# Display_Buttons.net
KiCad netlist of a schematic drawn in Altium Designer
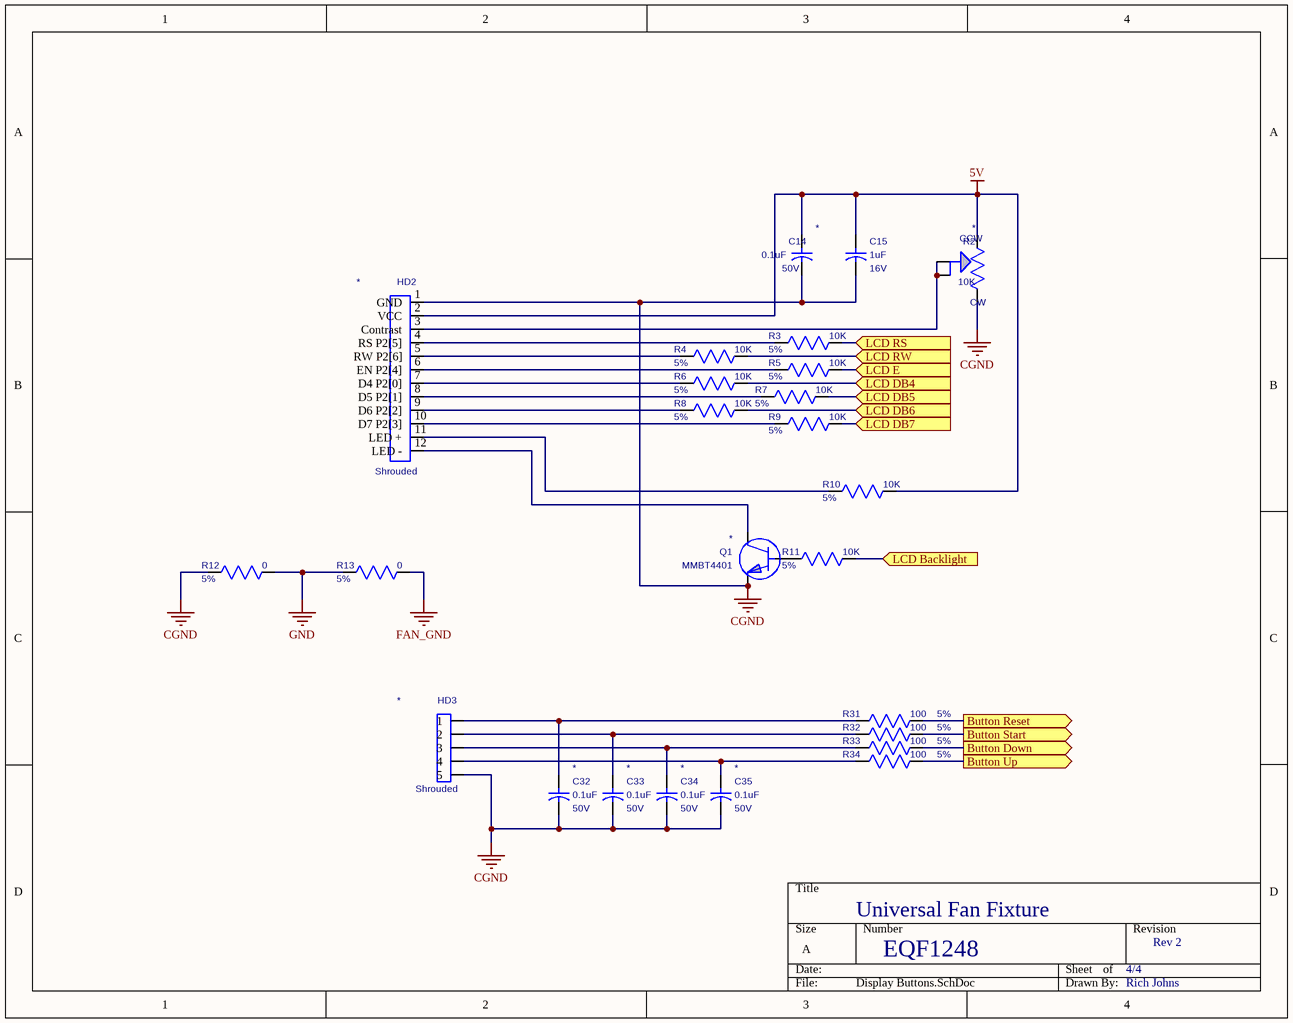
[diagram p0: Display Buttons.SchDoc]

(export (version "E")
  (design (tool "Eeschema 10.0.6"))
  (components
    (comp (ref "C14")
      (value "0.1uF")
      (footprint "0603")
      (fields
        (field (name "DNS") "*")
        (field (name "VOLTAGE") "50V")
        (field (name "TOLERANCE") "+/- 20%")
        (field (name "Comment") "CAP_NON_POLAR_SMT")
        (field (name "CHECKEDBY") "Sam Rhoufiry")
        (field (name "CREATEDBY") "Mike Tyger")
        (field (name "LASTUPDATEDBY") "Mike Tyger")
      )
      (libsource (lib "bome") (part "CAP_NON_POLAR_SMT"))
    )
    (comp (ref "C15")
      (value "1uF")
      (footprint "0603")
      (fields
        (field (name "TOLERANCE") "+/- 10%")
        (field (name "VOLTAGE") "16V")
        (field (name "Comment") "1.0uF_0603_16V")
        (field (name "CHECKEDBY") "gdeguzman")
        (field (name "LASTUPDATEDBY") "Rui Zhang")
      )
      (libsource (lib "bome") (part "1.0uF_0603_16V"))
    )
    (comp (ref "C32")
      (value "0.1uF")
      (footprint "0603")
      (fields
        (field (name "DNS") "*")
        (field (name "VOLTAGE") "50V")
        (field (name "TOLERANCE") "+/- 20%")
        (field (name "Comment") "CAP_NON_POLAR_SMT")
        (field (name "CHECKEDBY") "Sam Rhoufiry")
        (field (name "CREATEDBY") "Mike Tyger")
        (field (name "LASTUPDATEDBY") "Mike Tyger")
      )
      (libsource (lib "bome") (part "CAP_NON_POLAR_SMT"))
    )
    (comp (ref "C33")
      (value "0.1uF")
      (footprint "0603")
      (fields
        (field (name "DNS") "*")
        (field (name "VOLTAGE") "50V")
        (field (name "TOLERANCE") "+/- 20%")
        (field (name "Comment") "CAP_NON_POLAR_SMT")
        (field (name "CHECKEDBY") "Sam Rhoufiry")
        (field (name "CREATEDBY") "Mike Tyger")
        (field (name "LASTUPDATEDBY") "Mike Tyger")
      )
      (libsource (lib "bome") (part "CAP_NON_POLAR_SMT"))
    )
    (comp (ref "C34")
      (value "0.1uF")
      (footprint "0603")
      (fields
        (field (name "DNS") "*")
        (field (name "VOLTAGE") "50V")
        (field (name "TOLERANCE") "+/- 20%")
        (field (name "Comment") "CAP_NON_POLAR_SMT")
        (field (name "CHECKEDBY") "Sam Rhoufiry")
        (field (name "CREATEDBY") "Mike Tyger")
        (field (name "LASTUPDATEDBY") "Mike Tyger")
      )
      (libsource (lib "bome") (part "CAP_NON_POLAR_SMT"))
    )
    (comp (ref "C35")
      (value "0.1uF")
      (footprint "0603")
      (fields
        (field (name "DNS") "*")
        (field (name "VOLTAGE") "50V")
        (field (name "TOLERANCE") "+/- 20%")
        (field (name "Comment") "CAP_NON_POLAR_SMT")
        (field (name "CHECKEDBY") "Sam Rhoufiry")
        (field (name "CREATEDBY") "Mike Tyger")
        (field (name "LASTUPDATEDBY") "Mike Tyger")
      )
      (libsource (lib "bome") (part "CAP_NON_POLAR_SMT"))
    )
    (comp (ref "HD2")
      (value "HDR12PIN100SHRD")
      (footprint "HDR12PIN100SHRD")
      (description "Header, 0.1 in., 12 pins Pins, Shrouded, AMP: 1-64486-2")
      (fields
        (field (name "DNS") "*")
        (field (name "HEADERTYPE") "Shrouded")
        (field (name "CHECKEDBY") "Michael Angeli")
      )
      (libsource (lib "bome") (part "HDR12PIN100SHRD"))
    )
    (comp (ref "HD3")
      (value "HDR5PIN100SHRD")
      (footprint "HDR5PIN100SHRD")
      (description "Header, 0.100 in., 5 pin Pins, Shrouded, AMP: 644486-5")
      (fields
        (field (name "DNS") "*")
        (field (name "HEADERTYPE") "Shrouded")
        (field (name "CHECKEDBY") "Michael Angeli")
      )
      (libsource (lib "bome") (part "HDR5PIN100SHRD"))
    )
    (comp (ref "Q1")
      (value "MMBT4401")
      (footprint "SOT23-3")
      (description "Transistor, MMBT4401, 40V, SOT23-3, 500mA, NPN, Transistor, On Semi: MMBT4401LT1")
      (fields
        (field (name "DNS") "*")
        (field (name "VOLTAGE") "40V")
        (field (name "Comment") "NPN_TRANSISTOR")
        (field (name "CHECKEDBY") "gdeguzman")
        (field (name "CREATEDBY") "Mike Tyger")
        (field (name "LASTUPDATEDBY") "Mike Tyger")
      )
      (libsource (lib "bome") (part "NPN_TRANSISTOR"))
    )
    (comp (ref "R2")
      (value "10K")
      (footprint "6MM POT")
      (description "Resistor, 10K, Carbon, 20%, 0.2 in X 0.1 in or 0.2 in X 0.2 in, 0.1W, Panasonic: EVN-D8AA03B14")
      (fields
        (field (name "TOLERANCE") "20%")
        (field (name "DNS") "*")
        (field (name "Comment") "POT 6MM 10K")
        (field (name "CHECKEDBY") "B. Lyon")
      )
      (libsource (lib "bome") (part "POT 6MM 10K"))
    )
    (comp (ref "R3")
      (value "10K")
      (footprint "0603")
      (description "Resistor, 10K, ThickFilm, 5%, 0603, 1/10W, 2, Any")
      (fields
        (field (name "TOLERANCE") "5%")
        (field (name "Comment") "Resistor_0603_5%")
        (field (name "CHECKEDBY") "Joe Diffie")
        (field (name "LASTUPDATEDBY") "Rui Zhang")
      )
      (libsource (lib "bome") (part "Resistor_0603_5%"))
    )
    (comp (ref "R4")
      (value "10K")
      (footprint "0603")
      (description "Resistor, 10K, ThickFilm, 5%, 0603, 1/10W, 2, Any")
      (fields
        (field (name "TOLERANCE") "5%")
        (field (name "Comment") "Resistor_0603_5%")
        (field (name "CHECKEDBY") "Joe Diffie")
        (field (name "LASTUPDATEDBY") "Rui Zhang")
      )
      (libsource (lib "bome") (part "Resistor_0603_5%"))
    )
    (comp (ref "R5")
      (value "10K")
      (footprint "0603")
      (description "Resistor, 10K, ThickFilm, 5%, 0603, 1/10W, 2, Any")
      (fields
        (field (name "TOLERANCE") "5%")
        (field (name "Comment") "Resistor_0603_5%")
        (field (name "CHECKEDBY") "Joe Diffie")
        (field (name "LASTUPDATEDBY") "Rui Zhang")
      )
      (libsource (lib "bome") (part "Resistor_0603_5%"))
    )
    (comp (ref "R6")
      (value "10K")
      (footprint "0603")
      (description "Resistor, 10K, ThickFilm, 5%, 0603, 1/10W, 2, Any")
      (fields
        (field (name "TOLERANCE") "5%")
        (field (name "Comment") "Resistor_0603_5%")
        (field (name "CHECKEDBY") "Joe Diffie")
        (field (name "LASTUPDATEDBY") "Rui Zhang")
      )
      (libsource (lib "bome") (part "Resistor_0603_5%"))
    )
    (comp (ref "R7")
      (value "10K")
      (footprint "0603")
      (description "Resistor, 10K, ThickFilm, 5%, 0603, 1/10W, 2, Any")
      (fields
        (field (name "TOLERANCE") "5%")
        (field (name "Comment") "Resistor_0603_5%")
        (field (name "CHECKEDBY") "Joe Diffie")
        (field (name "LASTUPDATEDBY") "Rui Zhang")
      )
      (libsource (lib "bome") (part "Resistor_0603_5%"))
    )
    (comp (ref "R8")
      (value "10K")
      (footprint "0603")
      (description "Resistor, 10K, ThickFilm, 5%, 0603, 1/10W, 2, Any")
      (fields
        (field (name "TOLERANCE") "5%")
        (field (name "Comment") "Resistor_0603_5%")
        (field (name "CHECKEDBY") "Joe Diffie")
        (field (name "LASTUPDATEDBY") "Rui Zhang")
      )
      (libsource (lib "bome") (part "Resistor_0603_5%"))
    )
    (comp (ref "R9")
      (value "10K")
      (footprint "0603")
      (description "Resistor, 10K, ThickFilm, 5%, 0603, 1/10W, 2, Any")
      (fields
        (field (name "TOLERANCE") "5%")
        (field (name "Comment") "Resistor_0603_5%")
        (field (name "CHECKEDBY") "Joe Diffie")
        (field (name "LASTUPDATEDBY") "Rui Zhang")
      )
      (libsource (lib "bome") (part "Resistor_0603_5%"))
    )
    (comp (ref "R10")
      (value "10K")
      (footprint "0603")
      (description "Resistor, 10K, ThickFilm, 5%, 0603, 1/10W, 2, Any")
      (fields
        (field (name "TOLERANCE") "5%")
        (field (name "Comment") "Resistor_0603_5%")
        (field (name "CHECKEDBY") "Joe Diffie")
        (field (name "LASTUPDATEDBY") "Rui Zhang")
      )
      (libsource (lib "bome") (part "Resistor_0603_5%"))
    )
    (comp (ref "R11")
      (value "10K")
      (footprint "0603")
      (description "Resistor, 10K, ThickFilm, 5%, 0603, 1/10W, 2, Any")
      (fields
        (field (name "TOLERANCE") "5%")
        (field (name "Comment") "Resistor_0603_5%")
        (field (name "CHECKEDBY") "Joe Diffie")
        (field (name "LASTUPDATEDBY") "Rui Zhang")
      )
      (libsource (lib "bome") (part "Resistor_0603_5%"))
    )
    (comp (ref "R12")
      (value "0")
      (footprint "0603")
      (description "Resistor, 0, ThickFilm, 5%, 0603, 1/10W, 2, Any")
      (fields
        (field (name "TOLERANCE") "5%")
        (field (name "Comment") "Resistor_0603_5%")
        (field (name "CHECKEDBY") "Joe Diffie")
        (field (name "LASTUPDATEDBY") "Rui Zhang")
      )
      (libsource (lib "bome") (part "Resistor_0603_5%"))
    )
    (comp (ref "R13")
      (value "0")
      (footprint "0603")
      (description "Resistor, 0, ThickFilm, 5%, 0603, 1/10W, 2, Any")
      (fields
        (field (name "TOLERANCE") "5%")
        (field (name "Comment") "Resistor_0603_5%")
        (field (name "CHECKEDBY") "Joe Diffie")
        (field (name "LASTUPDATEDBY") "Rui Zhang")
      )
      (libsource (lib "bome") (part "Resistor_0603_5%"))
    )
    (comp (ref "R31")
      (value "100")
      (footprint "0603")
      (description "Resistor, 100, ThickFilm, 5%, 0603, 1/10W, 2, Any")
      (fields
        (field (name "TOLERANCE") "5%")
        (field (name "Comment") "Resistor_0603_5%")
        (field (name "CHECKEDBY") "Joe Diffie")
        (field (name "LASTUPDATEDBY") "Michael Angeli")
      )
      (libsource (lib "bome") (part "Resistor_0603_5%"))
    )
    (comp (ref "R32")
      (value "100")
      (footprint "0603")
      (description "Resistor, 100, ThickFilm, 5%, 0603, 1/10W, 2, Any")
      (fields
        (field (name "TOLERANCE") "5%")
        (field (name "Comment") "Resistor_0603_5%")
        (field (name "CHECKEDBY") "Joe Diffie")
        (field (name "LASTUPDATEDBY") "Michael Angeli")
      )
      (libsource (lib "bome") (part "Resistor_0603_5%"))
    )
    (comp (ref "R33")
      (value "100")
      (footprint "0603")
      (description "Resistor, 100, ThickFilm, 5%, 0603, 1/10W, 2, Any")
      (fields
        (field (name "TOLERANCE") "5%")
        (field (name "Comment") "Resistor_0603_5%")
        (field (name "CHECKEDBY") "Joe Diffie")
        (field (name "LASTUPDATEDBY") "Michael Angeli")
      )
      (libsource (lib "bome") (part "Resistor_0603_5%"))
    )
    (comp (ref "R34")
      (value "100")
      (footprint "0603")
      (description "Resistor, 100, ThickFilm, 5%, 0603, 1/10W, 2, Any")
      (fields
        (field (name "TOLERANCE") "5%")
        (field (name "Comment") "Resistor_0603_5%")
        (field (name "CHECKEDBY") "Joe Diffie")
        (field (name "LASTUPDATEDBY") "Michael Angeli")
      )
      (libsource (lib "bome") (part "Resistor_0603_5%"))
    )
  )
  (nets
    (net (code "1") (name "/Button Down") (class "Default")
      (node (ref "R33") (pin "1") (pinfunction "pin1_1") (pintype "passive"))
    )
    (net (code "2") (name "/Button Reset") (class "Default")
      (node (ref "R31") (pin "1") (pinfunction "pin1_1") (pintype "passive"))
    )
    (net (code "3") (name "/Button Start") (class "Default")
      (node (ref "R32") (pin "1") (pinfunction "pin1_1") (pintype "passive"))
    )
    (net (code "4") (name "/Button Up") (class "Default")
      (node (ref "R34") (pin "1") (pinfunction "pin1_1") (pintype "passive"))
    )
    (net (code "5") (name "/LCD Backlight") (class "Default")
      (node (ref "R11") (pin "1") (pinfunction "pin1_1") (pintype "passive"))
    )
    (net (code "6") (name "/LCD DB4") (class "Default")
      (node (ref "R6") (pin "1") (pinfunction "pin1_1") (pintype "passive"))
    )
    (net (code "7") (name "/LCD DB5") (class "Default")
      (node (ref "R7") (pin "1") (pinfunction "pin1_1") (pintype "passive"))
    )
    (net (code "8") (name "/LCD DB6") (class "Default")
      (node (ref "R8") (pin "1") (pinfunction "pin1_1") (pintype "passive"))
    )
    (net (code "9") (name "/LCD DB7") (class "Default")
      (node (ref "R9") (pin "1") (pinfunction "pin1_1") (pintype "passive"))
    )
    (net (code "10") (name "/LCD E") (class "Default")
      (node (ref "R5") (pin "1") (pinfunction "pin1_1") (pintype "passive"))
    )
    (net (code "11") (name "/LCD RS") (class "Default")
      (node (ref "R3") (pin "1") (pinfunction "pin1_1") (pintype "passive"))
    )
    (net (code "12") (name "/LCD RW") (class "Default")
      (node (ref "R4") (pin "1") (pinfunction "pin1_1") (pintype "passive"))
    )
    (net (code "13") (name "5V") (class "Default")
      (node (ref "C14") (pin "1") (pinfunction "pin1_1") (pintype "passive"))
      (node (ref "C15") (pin "1") (pinfunction "pin1_1") (pintype "passive"))
      (node (ref "HD2") (pin "2") (pinfunction "VCC_2") (pintype "passive"))
      (node (ref "R10") (pin "1") (pinfunction "pin1_1") (pintype "passive"))
      (node (ref "R2") (pin "1") (pinfunction "1_1") (pintype "passive"))
    )
    (net (code "14") (name "CGND") (class "Default")
      (node (ref "C14") (pin "2") (pinfunction "pin2_2") (pintype "passive"))
      (node (ref "C15") (pin "2") (pinfunction "pin2_2") (pintype "passive"))
      (node (ref "C32") (pin "2") (pinfunction "pin2_2") (pintype "passive"))
      (node (ref "C33") (pin "2") (pinfunction "pin2_2") (pintype "passive"))
      (node (ref "C34") (pin "2") (pinfunction "pin2_2") (pintype "passive"))
      (node (ref "C35") (pin "2") (pinfunction "pin2_2") (pintype "passive"))
      (node (ref "HD2") (pin "1") (pinfunction "GND_1") (pintype "passive"))
      (node (ref "HD3") (pin "5") (pinfunction "5_5") (pintype "passive"))
      (node (ref "Q1") (pin "2") (pinfunction "emitter_2") (pintype "passive"))
      (node (ref "R12") (pin "2") (pinfunction "pin2_2") (pintype "passive"))
      (node (ref "R2") (pin "4") (pinfunction "1_4") (pintype "passive"))
    )
    (net (code "15") (name "FAN_GND") (class "Default")
      (node (ref "R13") (pin "1") (pinfunction "pin1_1") (pintype "passive"))
    )
    (net (code "16") (name "GND") (class "Default")
      (node (ref "R12") (pin "1") (pinfunction "pin1_1") (pintype "passive"))
      (node (ref "R13") (pin "2") (pinfunction "pin2_2") (pintype "passive"))
    )
    (net (code "17") (name "Net-(C32-pin1)") (class "Default")
      (node (ref "C32") (pin "1") (pinfunction "pin1_1") (pintype "passive"))
      (node (ref "HD3") (pin "1") (pinfunction "1_1") (pintype "passive"))
      (node (ref "R31") (pin "2") (pinfunction "pin2_2") (pintype "passive"))
    )
    (net (code "18") (name "Net-(C33-pin1)") (class "Default")
      (node (ref "C33") (pin "1") (pinfunction "pin1_1") (pintype "passive"))
      (node (ref "HD3") (pin "2") (pinfunction "2_2") (pintype "passive"))
      (node (ref "R32") (pin "2") (pinfunction "pin2_2") (pintype "passive"))
    )
    (net (code "19") (name "Net-(C34-pin1)") (class "Default")
      (node (ref "C34") (pin "1") (pinfunction "pin1_1") (pintype "passive"))
      (node (ref "HD3") (pin "3") (pinfunction "3_3") (pintype "passive"))
      (node (ref "R33") (pin "2") (pinfunction "pin2_2") (pintype "passive"))
    )
    (net (code "20") (name "Net-(C35-pin1)") (class "Default")
      (node (ref "C35") (pin "1") (pinfunction "pin1_1") (pintype "passive"))
      (node (ref "HD3") (pin "4") (pinfunction "4_4") (pintype "passive"))
      (node (ref "R34") (pin "2") (pinfunction "pin2_2") (pintype "passive"))
    )
    (net (code "21") (name "Net-(HD2-Contrast)") (class "Default")
      (node (ref "HD2") (pin "3") (pinfunction "Contrast_3") (pintype "passive"))
      (node (ref "R2") (pin "2") (pinfunction "1_2") (pintype "passive"))
      (node (ref "R2") (pin "3") (pinfunction "1_3") (pintype "passive"))
    )
    (net (code "22") (name "Net-(HD2-D4_P2[0])") (class "Default")
      (node (ref "HD2") (pin "7") (pinfunction "D4_P2[0]_7") (pintype "passive"))
      (node (ref "R6") (pin "2") (pinfunction "pin2_2") (pintype "passive"))
    )
    (net (code "23") (name "Net-(HD2-D5_P2[1])") (class "Default")
      (node (ref "HD2") (pin "8") (pinfunction "D5_P2[1]_8") (pintype "passive"))
      (node (ref "R7") (pin "2") (pinfunction "pin2_2") (pintype "passive"))
    )
    (net (code "24") (name "Net-(HD2-D6_P2[2])") (class "Default")
      (node (ref "HD2") (pin "9") (pinfunction "D6_P2[2]_9") (pintype "passive"))
      (node (ref "R8") (pin "2") (pinfunction "pin2_2") (pintype "passive"))
    )
    (net (code "25") (name "Net-(HD2-D7_P2[3])") (class "Default")
      (node (ref "HD2") (pin "10") (pinfunction "D7_P2[3]_10") (pintype "passive"))
      (node (ref "R9") (pin "2") (pinfunction "pin2_2") (pintype "passive"))
    )
    (net (code "26") (name "Net-(HD2-EN_P2[4])") (class "Default")
      (node (ref "HD2") (pin "6") (pinfunction "EN_P2[4]_6") (pintype "passive"))
      (node (ref "R5") (pin "2") (pinfunction "pin2_2") (pintype "passive"))
    )
    (net (code "27") (name "Net-(HD2-LED_+)") (class "Default")
      (node (ref "HD2") (pin "11") (pinfunction "LED_+_11") (pintype "passive"))
      (node (ref "R10") (pin "2") (pinfunction "pin2_2") (pintype "passive"))
    )
    (net (code "28") (name "Net-(HD2-LED_-)") (class "Default")
      (node (ref "HD2") (pin "12") (pinfunction "LED_-_12") (pintype "passive"))
      (node (ref "Q1") (pin "3") (pinfunction "collector_3") (pintype "passive"))
    )
    (net (code "29") (name "Net-(HD2-RS_P2[5])") (class "Default")
      (node (ref "HD2") (pin "4") (pinfunction "RS_P2[5]_4") (pintype "passive"))
      (node (ref "R3") (pin "2") (pinfunction "pin2_2") (pintype "passive"))
    )
    (net (code "30") (name "Net-(HD2-RW_P2[6])") (class "Default")
      (node (ref "HD2") (pin "5") (pinfunction "RW_P2[6]_5") (pintype "passive"))
      (node (ref "R4") (pin "2") (pinfunction "pin2_2") (pintype "passive"))
    )
    (net (code "31") (name "Net-(Q1-base)") (class "Default")
      (node (ref "Q1") (pin "1") (pinfunction "base_1") (pintype "passive"))
      (node (ref "R11") (pin "2") (pinfunction "pin2_2") (pintype "passive"))
    )
    (net (code "32") (name "unconnected-(HD2-Pad13)") (class "Default")
      (node (ref "HD2") (pin "13") (pintype "passive"))
    )
    (net (code "33") (name "unconnected-(HD3-Pad6)") (class "Default")
      (node (ref "HD3") (pin "6") (pintype "passive"))
    )
  )
)
